# Leak_Detector_Remote_v1_0.net
KiCad netlist of a schematic drawn in EAGLE
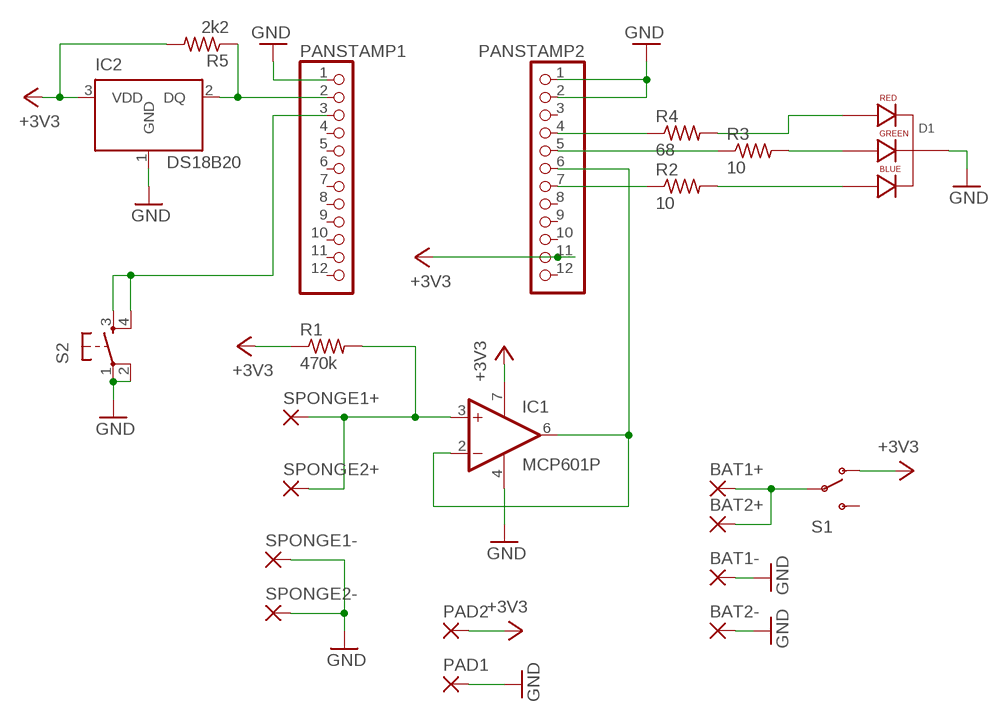
[diagram p0: schematic, sheet 1]

(export (version "E")
  (design (tool "Eeschema 10.0.6"))
  (components
    (comp (ref "BAT1+")
      (value "3,81/1,4")
      (footprint "eagle-import:3,81_1,4")
      (libsource (lib "eagle-import") (part "3,81/1,4"))
    )
    (comp (ref "BAT1-")
      (value "3,81/1,4")
      (footprint "eagle-import:3,81_1,4")
      (libsource (lib "eagle-import") (part "3,81/1,4"))
    )
    (comp (ref "BAT2+")
      (value "3,81/1,4")
      (footprint "eagle-import:3,81_1,4")
      (libsource (lib "eagle-import") (part "3,81/1,4"))
    )
    (comp (ref "BAT2-")
      (value "3,81/1,4")
      (footprint "eagle-import:3,81_1,4")
      (libsource (lib "eagle-import") (part "3,81/1,4"))
    )
    (comp (ref "D1")
      (value "LED-RGB-CC-THRUCLEAR")
      (footprint "eagle-import:LED-RGB-THRU")
      (libsource (lib "eagle-import") (part "LED-RGB-CC-THRUCLEAR"))
    )
    (comp (ref "IC1")
      (value "MCP601P")
      (footprint "eagle-import:DIL08")
      (libsource (lib "eagle-import") (part "MCP601P"))
    )
    (comp (ref "IC2")
      (value "DS18B20")
      (footprint "eagle-import:TO-92")
      (libsource (lib "eagle-import") (part "DS1820"))
    )
    (comp (ref "PAD1")
      (value "1,6/0,9")
      (footprint "eagle-import:1,6_0,9")
      (libsource (lib "eagle-import") (part "1,6/0,9"))
    )
    (comp (ref "PAD2")
      (value "1,6/0,9")
      (footprint "eagle-import:1,6_0,9")
      (libsource (lib "eagle-import") (part "1,6/0,9"))
    )
    (comp (ref "PANSTAMP1")
      (value "PINHD-1X12")
      (footprint "eagle-import:1X12")
      (libsource (lib "eagle-import") (part "PINHD-1X12"))
    )
    (comp (ref "PANSTAMP2")
      (value "PINHD-1X12")
      (footprint "eagle-import:1X12")
      (libsource (lib "eagle-import") (part "PINHD-1X12"))
    )
    (comp (ref "R1")
      (value "470k")
      (footprint "eagle-import:0204_7")
      (libsource (lib "eagle-import") (part "R-US_0204/7"))
    )
    (comp (ref "R2")
      (value "10")
      (footprint "eagle-import:0204_7")
      (libsource (lib "eagle-import") (part "R-US_0204/7"))
    )
    (comp (ref "R3")
      (value "10")
      (footprint "eagle-import:0204_7")
      (libsource (lib "eagle-import") (part "R-US_0204/7"))
    )
    (comp (ref "R4")
      (value "68")
      (footprint "eagle-import:0204_7")
      (libsource (lib "eagle-import") (part "R-US_0204/7"))
    )
    (comp (ref "R5")
      (value "2k2")
      (footprint "eagle-import:0204_7")
      (libsource (lib "eagle-import") (part "R-US_0204/7"))
    )
    (comp (ref "S1")
      (value "SWITCH-SPDTKIT")
      (footprint "eagle-import:SWITCH-SPDT_KIT")
      (libsource (lib "eagle-import") (part "SWITCH-SPDTKIT"))
    )
    (comp (ref "S2")
      (value "TAC_SWITCHPTH")
      (footprint "eagle-import:TACTILE-PTH")
      (libsource (lib "eagle-import") (part "TAC_SWITCHPTH"))
    )
    (comp (ref "SPONGE1+")
      (value "3,81/1,4")
      (footprint "eagle-import:3,81_1,4")
      (libsource (lib "eagle-import") (part "3,81/1,4"))
    )
    (comp (ref "SPONGE1-")
      (value "3,81/1,4")
      (footprint "eagle-import:3,81_1,4")
      (libsource (lib "eagle-import") (part "3,81/1,4"))
    )
    (comp (ref "SPONGE2+")
      (value "3,81/1,4")
      (footprint "eagle-import:3,81_1,4")
      (libsource (lib "eagle-import") (part "3,81/1,4"))
    )
    (comp (ref "SPONGE2-")
      (value "3,81/1,4")
      (footprint "eagle-import:3,81_1,4")
      (libsource (lib "eagle-import") (part "3,81/1,4"))
    )
  )
  (nets
    (net (code "1") (name "+3V3") (class "Default")
      (node (ref "IC1") (pin "7") (pinfunction "V+_7") (pintype "power_in"))
      (node (ref "IC2") (pin "3") (pinfunction "VDD_3") (pintype "input"))
      (node (ref "PAD2") (pin "1") (pinfunction "P_1") (pintype "passive"))
      (node (ref "PANSTAMP2") (pin "11") (pinfunction "11_11") (pintype "passive"))
      (node (ref "R1") (pin "1") (pinfunction "1_1") (pintype "passive"))
      (node (ref "R5") (pin "2") (pinfunction "2_2") (pintype "passive"))
      (node (ref "S1") (pin "1") (pinfunction "O_1") (pintype "passive"))
    )
    (net (code "2") (name "GND") (class "Default")
      (node (ref "BAT1-") (pin "1") (pinfunction "P_1") (pintype "passive"))
      (node (ref "BAT2-") (pin "1") (pinfunction "P_1") (pintype "passive"))
      (node (ref "D1") (pin "2") (pinfunction "CATHODE_2") (pintype "bidirectional"))
      (node (ref "IC1") (pin "4") (pinfunction "V-_4") (pintype "power_in"))
      (node (ref "IC2") (pin "1") (pinfunction "GND_1") (pintype "power_in"))
      (node (ref "PAD1") (pin "1") (pinfunction "P_1") (pintype "passive"))
      (node (ref "PANSTAMP1") (pin "1") (pinfunction "1_1") (pintype "passive"))
      (node (ref "PANSTAMP2") (pin "1") (pinfunction "1_1") (pintype "passive"))
      (node (ref "PANSTAMP2") (pin "2") (pinfunction "2_2") (pintype "passive"))
      (node (ref "S2") (pin "1") (pinfunction "1_1") (pintype "passive"))
      (node (ref "S2") (pin "2") (pinfunction "2_2") (pintype "passive"))
      (node (ref "SPONGE1-") (pin "1") (pinfunction "P_1") (pintype "passive"))
      (node (ref "SPONGE2-") (pin "1") (pinfunction "P_1") (pintype "passive"))
    )
    (net (code "3") (name "Net-(BAT1+-P)") (class "Default")
      (node (ref "BAT1+") (pin "1") (pinfunction "P_1") (pintype "passive"))
      (node (ref "BAT2+") (pin "1") (pinfunction "P_1") (pintype "passive"))
      (node (ref "S1") (pin "2") (pinfunction "P_2") (pintype "passive"))
    )
    (net (code "4") (name "Net-(D1-BLUE_CATHODE)") (class "Default")
      (node (ref "D1") (pin "4") (pinfunction "BLUE_CATHODE_4") (pintype "bidirectional"))
      (node (ref "R2") (pin "2") (pinfunction "2_2") (pintype "passive"))
    )
    (net (code "5") (name "Net-(D1-GREEN_CATHODE)") (class "Default")
      (node (ref "D1") (pin "3") (pinfunction "GREEN_CATHODE_3") (pintype "bidirectional"))
      (node (ref "R3") (pin "2") (pinfunction "2_2") (pintype "passive"))
    )
    (net (code "6") (name "Net-(D1-RED_CATHODE)") (class "Default")
      (node (ref "D1") (pin "1") (pinfunction "RED_CATHODE_1") (pintype "bidirectional"))
      (node (ref "R4") (pin "2") (pinfunction "2_2") (pintype "passive"))
    )
    (net (code "7") (name "Net-(IC1-+IN)") (class "Default")
      (node (ref "IC1") (pin "3") (pinfunction "+IN_3") (pintype "input"))
      (node (ref "R1") (pin "2") (pinfunction "2_2") (pintype "passive"))
      (node (ref "SPONGE1+") (pin "1") (pinfunction "P_1") (pintype "passive"))
      (node (ref "SPONGE2+") (pin "1") (pinfunction "P_1") (pintype "passive"))
    )
    (net (code "8") (name "Net-(IC1--IN)") (class "Default")
      (node (ref "IC1") (pin "2") (pinfunction "-IN_2") (pintype "input"))
      (node (ref "IC1") (pin "6") (pinfunction "OUT_6") (pintype "output"))
      (node (ref "PANSTAMP2") (pin "6") (pinfunction "6_6") (pintype "passive"))
    )
    (net (code "9") (name "Net-(IC2-DQ)") (class "Default")
      (node (ref "IC2") (pin "2") (pinfunction "DQ_2") (pintype "output"))
      (node (ref "PANSTAMP1") (pin "2") (pinfunction "2_2") (pintype "passive"))
      (node (ref "R5") (pin "1") (pinfunction "1_1") (pintype "passive"))
    )
    (net (code "10") (name "Net-(PANSTAMP1-Pad3)") (class "Default")
      (node (ref "PANSTAMP1") (pin "3") (pinfunction "3_3") (pintype "passive"))
      (node (ref "S2") (pin "3") (pinfunction "3_3") (pintype "passive"))
      (node (ref "S2") (pin "4") (pinfunction "4_4") (pintype "passive"))
    )
    (net (code "11") (name "Net-(PANSTAMP2-Pad4)") (class "Default")
      (node (ref "PANSTAMP2") (pin "4") (pinfunction "4_4") (pintype "passive"))
      (node (ref "R4") (pin "1") (pinfunction "1_1") (pintype "passive"))
    )
    (net (code "12") (name "Net-(PANSTAMP2-Pad5)") (class "Default")
      (node (ref "PANSTAMP2") (pin "5") (pinfunction "5_5") (pintype "passive"))
      (node (ref "R3") (pin "1") (pinfunction "1_1") (pintype "passive"))
    )
    (net (code "13") (name "Net-(PANSTAMP2-Pad7)") (class "Default")
      (node (ref "PANSTAMP2") (pin "7") (pinfunction "7_7") (pintype "passive"))
      (node (ref "R2") (pin "1") (pinfunction "1_1") (pintype "passive"))
    )
    (net (code "14") (name "unconnected-(PANSTAMP1-Pad4)") (class "Default")
      (node (ref "PANSTAMP1") (pin "4") (pinfunction "4_4") (pintype "passive"))
    )
    (net (code "15") (name "unconnected-(PANSTAMP1-Pad5)") (class "Default")
      (node (ref "PANSTAMP1") (pin "5") (pinfunction "5_5") (pintype "passive"))
    )
    (net (code "16") (name "unconnected-(PANSTAMP1-Pad6)") (class "Default")
      (node (ref "PANSTAMP1") (pin "6") (pinfunction "6_6") (pintype "passive"))
    )
    (net (code "17") (name "unconnected-(PANSTAMP1-Pad7)") (class "Default")
      (node (ref "PANSTAMP1") (pin "7") (pinfunction "7_7") (pintype "passive"))
    )
    (net (code "18") (name "unconnected-(PANSTAMP1-Pad8)") (class "Default")
      (node (ref "PANSTAMP1") (pin "8") (pinfunction "8_8") (pintype "passive"))
    )
    (net (code "19") (name "unconnected-(PANSTAMP1-Pad9)") (class "Default")
      (node (ref "PANSTAMP1") (pin "9") (pinfunction "9_9") (pintype "passive"))
    )
    (net (code "20") (name "unconnected-(PANSTAMP1-Pad10)") (class "Default")
      (node (ref "PANSTAMP1") (pin "10") (pinfunction "10_10") (pintype "passive"))
    )
    (net (code "21") (name "unconnected-(PANSTAMP1-Pad11)") (class "Default")
      (node (ref "PANSTAMP1") (pin "11") (pinfunction "11_11") (pintype "passive"))
    )
    (net (code "22") (name "unconnected-(PANSTAMP1-Pad12)") (class "Default")
      (node (ref "PANSTAMP1") (pin "12") (pinfunction "12_12") (pintype "passive"))
    )
    (net (code "23") (name "unconnected-(PANSTAMP2-Pad3)") (class "Default")
      (node (ref "PANSTAMP2") (pin "3") (pinfunction "3_3") (pintype "passive"))
    )
    (net (code "24") (name "unconnected-(PANSTAMP2-Pad8)") (class "Default")
      (node (ref "PANSTAMP2") (pin "8") (pinfunction "8_8") (pintype "passive"))
    )
    (net (code "25") (name "unconnected-(PANSTAMP2-Pad9)") (class "Default")
      (node (ref "PANSTAMP2") (pin "9") (pinfunction "9_9") (pintype "passive"))
    )
    (net (code "26") (name "unconnected-(PANSTAMP2-Pad10)") (class "Default")
      (node (ref "PANSTAMP2") (pin "10") (pinfunction "10_10") (pintype "passive"))
    )
    (net (code "27") (name "unconnected-(PANSTAMP2-Pad12)") (class "Default")
      (node (ref "PANSTAMP2") (pin "12") (pinfunction "12_12") (pintype "passive"))
    )
    (net (code "28") (name "unconnected-(S1-S-Pad3)") (class "Default")
      (node (ref "S1") (pin "3") (pinfunction "S_3") (pintype "passive"))
    )
  )
)
